# RelayBoard.net
KiCad netlist of a schematic drawn in Altium Designer
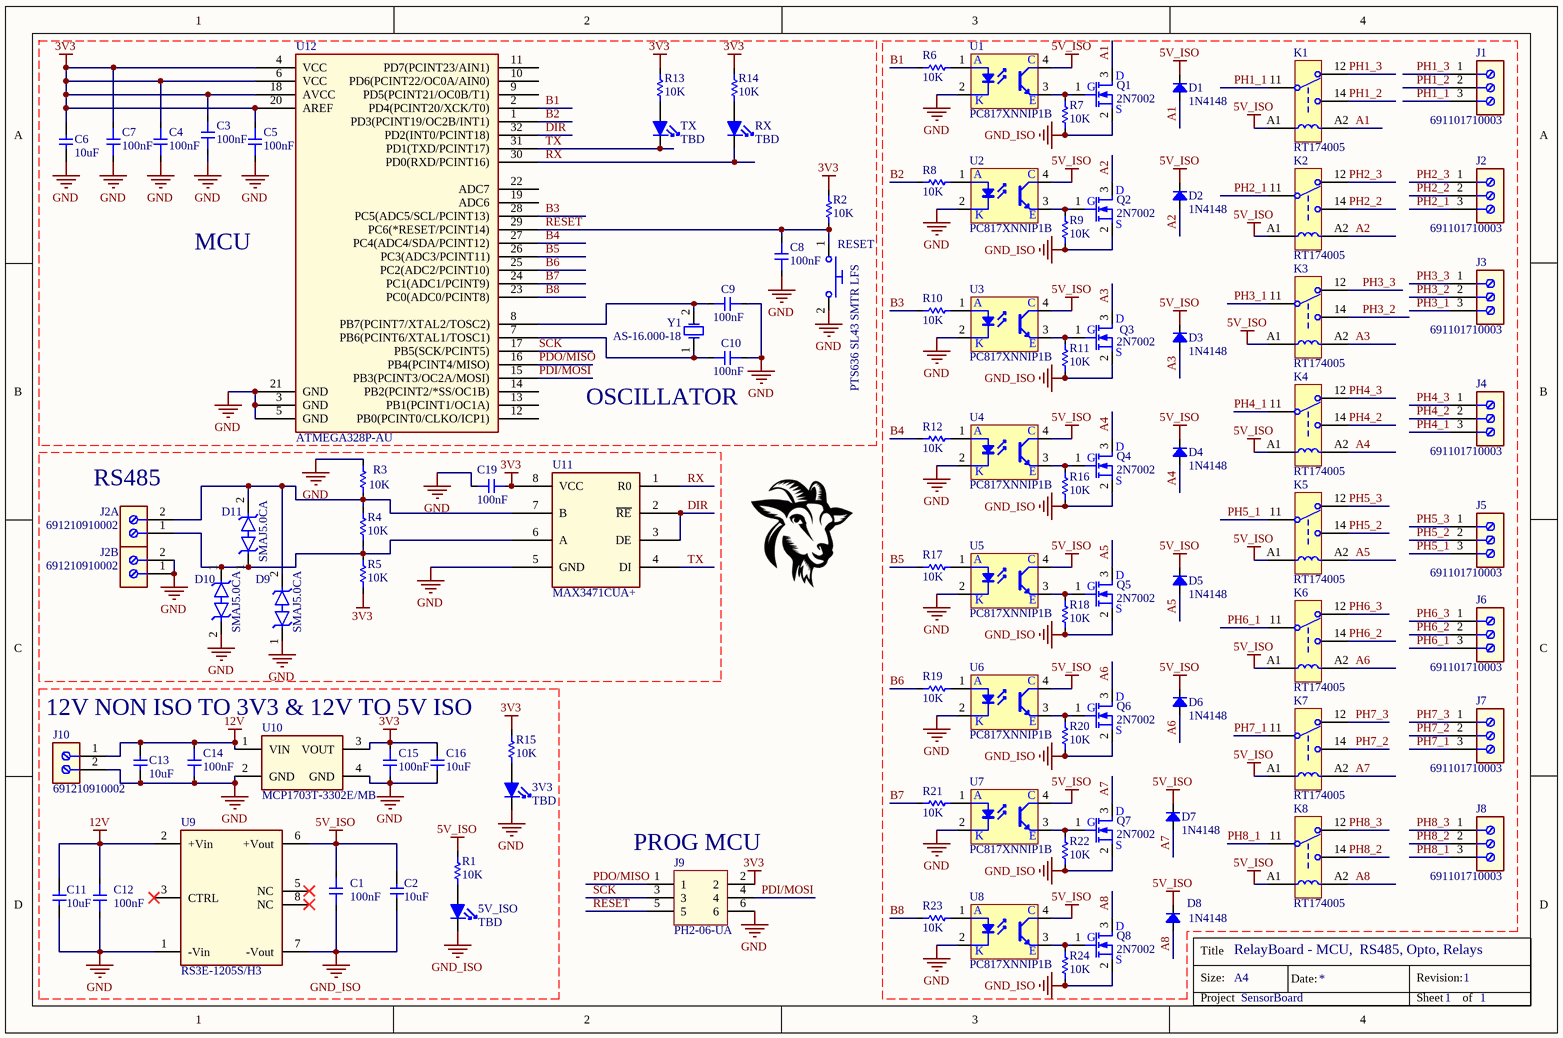
[diagram p0: RelayBoard.SchDoc]

(export (version "E")
  (design (tool "Eeschema 10.0.6"))
  (components
    (comp (ref "3V3")
      (value "TBD")
      (footprint "CASE0603")
      (description "Typical INFRARED GaAs LED")
      (libsource (lib "RelayBoard") (part "LED"))
    )
    (comp (ref "5V_ISO")
      (value "TBD")
      (footprint "CASE0603")
      (description "Typical INFRARED GaAs LED")
      (libsource (lib "RelayBoard") (part "LED"))
    )
    (comp (ref "C1")
      (value "100nF")
      (footprint "CASE0603")
      (description "CAP CER 100nF 5% 25V X7R 0603")
      (fields (field (name "MFR") "KEMET"))
      (libsource (lib "RelayBoard") (part "Capacitor_100nF"))
    )
    (comp (ref "C2")
      (value "10uF")
      (footprint "CASE0603")
      (description "CAP CER 10uF 20% 25V X5R 0603")
      (fields (field (name "MFR") "TDK"))
      (libsource (lib "RelayBoard") (part "Capacitor_10uF"))
    )
    (comp (ref "C3")
      (value "100nF")
      (footprint "CASE0603")
      (description "CAP CER 100nF 5% 25V X7R 0603")
      (fields (field (name "MFR") "KEMET"))
      (libsource (lib "RelayBoard") (part "Capacitor_100nF"))
    )
    (comp (ref "C4")
      (value "100nF")
      (footprint "CASE0603")
      (description "CAP CER 100nF 5% 25V X7R 0603")
      (fields (field (name "MFR") "KEMET"))
      (libsource (lib "RelayBoard") (part "Capacitor_100nF"))
    )
    (comp (ref "C5")
      (value "100nF")
      (footprint "CASE0603")
      (description "CAP CER 100nF 5% 25V X7R 0603")
      (fields (field (name "MFR") "KEMET"))
      (libsource (lib "RelayBoard") (part "Capacitor_100nF"))
    )
    (comp (ref "C6")
      (value "10uF")
      (footprint "CASE0603")
      (description "CAP CER 10uF 20% 25V X5R 0603")
      (fields (field (name "MFR") "TDK"))
      (libsource (lib "RelayBoard") (part "Capacitor_10uF"))
    )
    (comp (ref "C7")
      (value "100nF")
      (footprint "CASE0603")
      (description "CAP CER 100nF 5% 25V X7R 0603")
      (fields (field (name "MFR") "KEMET"))
      (libsource (lib "RelayBoard") (part "Capacitor_100nF"))
    )
    (comp (ref "C8")
      (value "100nF")
      (footprint "CASE0603")
      (description "CAP CER 100nF 5% 25V X7R 0603")
      (fields (field (name "MFR") "KEMET"))
      (libsource (lib "RelayBoard") (part "Capacitor_100nF"))
    )
    (comp (ref "C9")
      (value "100nF")
      (footprint "CASE0603")
      (description "CAP CER 100nF 5% 25V X7R 0603")
      (fields (field (name "MFR") "KEMET"))
      (libsource (lib "RelayBoard") (part "Capacitor_100nF"))
    )
    (comp (ref "C10")
      (value "100nF")
      (footprint "CASE0603")
      (description "CAP CER 100nF 5% 25V X7R 0603")
      (fields (field (name "MFR") "KEMET"))
      (libsource (lib "RelayBoard") (part "Capacitor_100nF"))
    )
    (comp (ref "C11")
      (value "10uF")
      (footprint "CASE0603")
      (description "CAP CER 10uF 20% 25V X5R 0603")
      (fields (field (name "MFR") "TDK"))
      (libsource (lib "RelayBoard") (part "Capacitor_10uF"))
    )
    (comp (ref "C12")
      (value "100nF")
      (footprint "CASE0603")
      (description "CAP CER 100nF 5% 25V X7R 0603")
      (fields (field (name "MFR") "KEMET"))
      (libsource (lib "RelayBoard") (part "Capacitor_100nF"))
    )
    (comp (ref "C13")
      (value "10uF")
      (footprint "CASE0603")
      (description "CAP CER 10uF 20% 25V X5R 0603")
      (fields (field (name "MFR") "TDK"))
      (libsource (lib "RelayBoard") (part "Capacitor_10uF"))
    )
    (comp (ref "C14")
      (value "100nF")
      (footprint "CASE0603")
      (description "CAP CER 100nF 5% 25V X7R 0603")
      (fields (field (name "MFR") "KEMET"))
      (libsource (lib "RelayBoard") (part "Capacitor_100nF"))
    )
    (comp (ref "C15")
      (value "100nF")
      (footprint "CASE0603")
      (description "CAP CER 100nF 5% 25V X7R 0603")
      (fields (field (name "MFR") "KEMET"))
      (libsource (lib "RelayBoard") (part "Capacitor_100nF"))
    )
    (comp (ref "C16")
      (value "10uF")
      (footprint "CASE0603")
      (description "CAP CER 10uF 20% 25V X5R 0603")
      (fields (field (name "MFR") "TDK"))
      (libsource (lib "RelayBoard") (part "Capacitor_10uF"))
    )
    (comp (ref "C19")
      (value "100nF")
      (footprint "CASE0603")
      (description "CAP CER 100nF 5% 25V X7R 0603")
      (fields (field (name "MFR") "KEMET"))
      (libsource (lib "RelayBoard") (part "Capacitor_100nF"))
    )
    (comp (ref "D1")
      (value "1N4148")
      (footprint "SOD-323")
      (description "High Conductance Fast Diode")
      (fields (field (name "MFR") "Micro Commercial Components (MCC)"))
      (libsource (lib "RelayBoard") (part "Diode 1N4148"))
    )
    (comp (ref "D2")
      (value "1N4148")
      (footprint "SOD-323")
      (description "High Conductance Fast Diode")
      (fields (field (name "MFR") "Micro Commercial Components (MCC)"))
      (libsource (lib "RelayBoard") (part "Diode 1N4148"))
    )
    (comp (ref "D3")
      (value "1N4148")
      (footprint "SOD-323")
      (description "High Conductance Fast Diode")
      (fields (field (name "MFR") "Micro Commercial Components (MCC)"))
      (libsource (lib "RelayBoard") (part "Diode 1N4148"))
    )
    (comp (ref "D4")
      (value "1N4148")
      (footprint "SOD-323")
      (description "High Conductance Fast Diode")
      (fields (field (name "MFR") "Micro Commercial Components (MCC)"))
      (libsource (lib "RelayBoard") (part "Diode 1N4148"))
    )
    (comp (ref "D5")
      (value "1N4148")
      (footprint "SOD-323")
      (description "High Conductance Fast Diode")
      (fields (field (name "MFR") "Micro Commercial Components (MCC)"))
      (libsource (lib "RelayBoard") (part "Diode 1N4148"))
    )
    (comp (ref "D6")
      (value "1N4148")
      (footprint "SOD-323")
      (description "High Conductance Fast Diode")
      (fields (field (name "MFR") "Micro Commercial Components (MCC)"))
      (libsource (lib "RelayBoard") (part "Diode 1N4148"))
    )
    (comp (ref "D7")
      (value "1N4148")
      (footprint "SOD-323")
      (description "High Conductance Fast Diode")
      (fields (field (name "MFR") "Micro Commercial Components (MCC)"))
      (libsource (lib "RelayBoard") (part "Diode 1N4148"))
    )
    (comp (ref "D8")
      (value "1N4148")
      (footprint "SOD-323")
      (description "High Conductance Fast Diode")
      (fields (field (name "MFR") "Micro Commercial Components (MCC)"))
      (libsource (lib "RelayBoard") (part "Diode 1N4148"))
    )
    (comp (ref "D9")
      (value "SMAJ5.0CA")
      (footprint "SMA")
      (description "9.2V Clamp 43.5A Ipp Tvs Diode Surface Mount DO-214AC (SMA)")
      (fields (field (name "MFR") "Good-Ark Semiconductor"))
      (libsource (lib "RelayBoard") (part "Diode_SMAJ5.0CA"))
    )
    (comp (ref "D10")
      (value "SMAJ5.0CA")
      (footprint "SMA")
      (description "9.2V Clamp 43.5A Ipp Tvs Diode Surface Mount DO-214AC (SMA)")
      (fields (field (name "MFR") "Good-Ark Semiconductor"))
      (libsource (lib "RelayBoard") (part "Diode_SMAJ5.0CA"))
    )
    (comp (ref "D11")
      (value "SMAJ5.0CA")
      (footprint "SMA")
      (description "9.2V Clamp 43.5A Ipp Tvs Diode Surface Mount DO-214AC (SMA)")
      (fields (field (name "MFR") "Good-Ark Semiconductor"))
      (libsource (lib "RelayBoard") (part "Diode_SMAJ5.0CA"))
    )
    (comp (ref "J1")
      (value "691101710003")
      (footprint "691101710003")
      (description "TERM BLOCK 3P HORIZON 5MM PCB")
      (fields (field (name "MFR") "Wurth"))
      (libsource (lib "RelayBoard") (part "Connector_691101710003"))
    )
    (comp (ref "J2")
      (value "691101710003")
      (footprint "691101710003")
      (description "TERM BLOCK 3P HORIZON 5MM PCB")
      (fields (field (name "MFR") "Wurth"))
      (libsource (lib "RelayBoard") (part "Connector_691101710003"))
    )
    (comp (ref "J2A")
      (value "691210910002")
      (footprint "691210910002")
      (description "TERM BLOCK 2P HORIZON 2.54MM PCB")
      (fields (field (name "MFR") "Wurth"))
      (libsource (lib "RelayBoard") (part "Connector_691210910002"))
    )
    (comp (ref "J2B")
      (value "691210910002")
      (footprint "691210910002")
      (description "TERM BLOCK 2P HORIZON 2.54MM PCB")
      (fields (field (name "MFR") "Wurth"))
      (libsource (lib "RelayBoard") (part "Connector_691210910002"))
    )
    (comp (ref "J3")
      (value "691101710003")
      (footprint "691101710003")
      (description "TERM BLOCK 3P HORIZON 5MM PCB")
      (fields (field (name "MFR") "Wurth"))
      (libsource (lib "RelayBoard") (part "Connector_691101710003"))
    )
    (comp (ref "J4")
      (value "691101710003")
      (footprint "691101710003")
      (description "TERM BLOCK 3P HORIZON 5MM PCB")
      (fields (field (name "MFR") "Wurth"))
      (libsource (lib "RelayBoard") (part "Connector_691101710003"))
    )
    (comp (ref "J5")
      (value "691101710003")
      (footprint "691101710003")
      (description "TERM BLOCK 3P HORIZON 5MM PCB")
      (fields (field (name "MFR") "Wurth"))
      (libsource (lib "RelayBoard") (part "Connector_691101710003"))
    )
    (comp (ref "J6")
      (value "691101710003")
      (footprint "691101710003")
      (description "TERM BLOCK 3P HORIZON 5MM PCB")
      (fields (field (name "MFR") "Wurth"))
      (libsource (lib "RelayBoard") (part "Connector_691101710003"))
    )
    (comp (ref "J7")
      (value "691101710003")
      (footprint "691101710003")
      (description "TERM BLOCK 3P HORIZON 5MM PCB")
      (fields (field (name "MFR") "Wurth"))
      (libsource (lib "RelayBoard") (part "Connector_691101710003"))
    )
    (comp (ref "J8")
      (value "691101710003")
      (footprint "691101710003")
      (description "TERM BLOCK 3P HORIZON 5MM PCB")
      (fields (field (name "MFR") "Wurth"))
      (libsource (lib "RelayBoard") (part "Connector_691101710003"))
    )
    (comp (ref "J9")
      (value "PH2-06-UA")
      (footprint "Header_2x3_2.54_Male")
      (description "Connector Header Through Hole 6 position 0.100\" (2.54mm)")
      (fields (field (name "MFR") "Adam Tech"))
      (libsource (lib "RelayBoard") (part "Connector_PH2-06-UA"))
    )
    (comp (ref "J10")
      (value "691210910002")
      (footprint "691210910002")
      (description "TERM BLOCK 2P HORIZON 2.54MM PCB")
      (fields (field (name "MFR") "Wurth"))
      (libsource (lib "") (part "Connector_691210910002_1"))
    )
    (comp (ref "K1")
      (value "RT174005")
      (footprint "RELAY-SPDT_3.5mm")
      (description "RELAY GEN PURPOSE SPDT 10A 5V")
      (fields (field (name "MFR") "TE"))
      (libsource (lib "RelayBoard") (part "Relay_RT174005"))
    )
    (comp (ref "K2")
      (value "RT174005")
      (footprint "RELAY-SPDT_3.5mm")
      (description "RELAY GEN PURPOSE SPDT 10A 5V")
      (fields (field (name "MFR") "TE"))
      (libsource (lib "RelayBoard") (part "Relay_RT174005"))
    )
    (comp (ref "K3")
      (value "RT174005")
      (footprint "RELAY-SPDT_3.5mm")
      (description "RELAY GEN PURPOSE SPDT 10A 5V")
      (fields (field (name "MFR") "TE"))
      (libsource (lib "RelayBoard") (part "Relay_RT174005"))
    )
    (comp (ref "K4")
      (value "RT174005")
      (footprint "RELAY-SPDT_3.5mm")
      (description "RELAY GEN PURPOSE SPDT 10A 5V")
      (fields (field (name "MFR") "TE"))
      (libsource (lib "RelayBoard") (part "Relay_RT174005"))
    )
    (comp (ref "K5")
      (value "RT174005")
      (footprint "RELAY-SPDT_3.5mm")
      (description "RELAY GEN PURPOSE SPDT 10A 5V")
      (fields (field (name "MFR") "TE"))
      (libsource (lib "RelayBoard") (part "Relay_RT174005"))
    )
    (comp (ref "K6")
      (value "RT174005")
      (footprint "RELAY-SPDT_3.5mm")
      (description "RELAY GEN PURPOSE SPDT 10A 5V")
      (fields (field (name "MFR") "TE"))
      (libsource (lib "RelayBoard") (part "Relay_RT174005"))
    )
    (comp (ref "K7")
      (value "RT174005")
      (footprint "RELAY-SPDT_3.5mm")
      (description "RELAY GEN PURPOSE SPDT 10A 5V")
      (fields (field (name "MFR") "TE"))
      (libsource (lib "RelayBoard") (part "Relay_RT174005"))
    )
    (comp (ref "K8")
      (value "RT174005")
      (footprint "RELAY-SPDT_3.5mm")
      (description "RELAY GEN PURPOSE SPDT 10A 5V")
      (fields (field (name "MFR") "TE"))
      (libsource (lib "RelayBoard") (part "Relay_RT174005"))
    )
    (comp (ref "Q1")
      (value "2N7002")
      (footprint "SOT23-3")
      (description "MOSFET N-CH 60V 280MA SOT23-3")
      (fields (field (name "MFR") "Microchip"))
      (libsource (lib "RelayBoard") (part "Transistor_NMOS"))
    )
    (comp (ref "Q2")
      (value "2N7002")
      (footprint "SOT23-3")
      (description "MOSFET N-CH 60V 280MA SOT23-3")
      (fields (field (name "MFR") "Microchip"))
      (libsource (lib "RelayBoard") (part "Transistor_NMOS"))
    )
    (comp (ref "Q3")
      (value "2N7002")
      (footprint "SOT23-3")
      (description "MOSFET N-CH 60V 280MA SOT23-3")
      (fields (field (name "MFR") "Microchip"))
      (libsource (lib "RelayBoard") (part "Transistor_NMOS"))
    )
    (comp (ref "Q4")
      (value "2N7002")
      (footprint "SOT23-3")
      (description "MOSFET N-CH 60V 280MA SOT23-3")
      (fields (field (name "MFR") "Microchip"))
      (libsource (lib "RelayBoard") (part "Transistor_NMOS"))
    )
    (comp (ref "Q5")
      (value "2N7002")
      (footprint "SOT23-3")
      (description "MOSFET N-CH 60V 280MA SOT23-3")
      (fields (field (name "MFR") "Microchip"))
      (libsource (lib "RelayBoard") (part "Transistor_NMOS"))
    )
    (comp (ref "Q6")
      (value "2N7002")
      (footprint "SOT23-3")
      (description "MOSFET N-CH 60V 280MA SOT23-3")
      (fields (field (name "MFR") "Microchip"))
      (libsource (lib "RelayBoard") (part "Transistor_NMOS"))
    )
    (comp (ref "Q7")
      (value "2N7002")
      (footprint "SOT23-3")
      (description "MOSFET N-CH 60V 280MA SOT23-3")
      (fields (field (name "MFR") "Microchip"))
      (libsource (lib "RelayBoard") (part "Transistor_NMOS"))
    )
    (comp (ref "Q8")
      (value "2N7002")
      (footprint "SOT23-3")
      (description "MOSFET N-CH 60V 280MA SOT23-3")
      (fields (field (name "MFR") "Microchip"))
      (libsource (lib "RelayBoard") (part "Transistor_NMOS"))
    )
    (comp (ref "R1")
      (value "10K")
      (footprint "CASE0603")
      (description "RES 10K 1% 1/10W 0603")
      (fields (field (name "MFR") "YAGEO"))
      (libsource (lib "RelayBoard") (part "Resistor_10K_0603"))
    )
    (comp (ref "R2")
      (value "10K")
      (footprint "CASE0603")
      (description "RES 10K 1% 1/10W 0603")
      (fields (field (name "MFR") "YAGEO"))
      (libsource (lib "RelayBoard") (part "Resistor_10K_0603"))
    )
    (comp (ref "R3")
      (value "10K")
      (footprint "CASE0603")
      (description "RES 10K 1% 1/10W 0603")
      (fields (field (name "MFR") "YAGEO"))
      (libsource (lib "RelayBoard") (part "Resistor_10K_0603"))
    )
    (comp (ref "R4")
      (value "10K")
      (footprint "CASE0603")
      (description "RES 10K 1% 1/10W 0603")
      (fields (field (name "MFR") "YAGEO"))
      (libsource (lib "RelayBoard") (part "Resistor_10K_0603"))
    )
    (comp (ref "R5")
      (value "10K")
      (footprint "CASE0603")
      (description "RES 10K 1% 1/10W 0603")
      (fields (field (name "MFR") "YAGEO"))
      (libsource (lib "RelayBoard") (part "Resistor_10K_0603"))
    )
    (comp (ref "R6")
      (value "10K")
      (footprint "CASE0603")
      (description "RES 10K 1% 1/10W 0603")
      (fields (field (name "MFR") "YAGEO"))
      (libsource (lib "RelayBoard") (part "Resistor_10K_0603"))
    )
    (comp (ref "R7")
      (value "10K")
      (footprint "CASE0603")
      (description "RES 10K 1% 1/10W 0603")
      (fields (field (name "MFR") "YAGEO"))
      (libsource (lib "RelayBoard") (part "Resistor_10K_0603"))
    )
    (comp (ref "R8")
      (value "10K")
      (footprint "CASE0603")
      (description "RES 10K 1% 1/10W 0603")
      (fields (field (name "MFR") "YAGEO"))
      (libsource (lib "RelayBoard") (part "Resistor_10K_0603"))
    )
    (comp (ref "R9")
      (value "10K")
      (footprint "CASE0603")
      (description "RES 10K 1% 1/10W 0603")
      (fields (field (name "MFR") "YAGEO"))
      (libsource (lib "RelayBoard") (part "Resistor_10K_0603"))
    )
    (comp (ref "R10")
      (value "10K")
      (footprint "CASE0603")
      (description "RES 10K 1% 1/10W 0603")
      (fields (field (name "MFR") "YAGEO"))
      (libsource (lib "RelayBoard") (part "Resistor_10K_0603"))
    )
    (comp (ref "R11")
      (value "10K")
      (footprint "CASE0603")
      (description "RES 10K 1% 1/10W 0603")
      (fields (field (name "MFR") "YAGEO"))
      (libsource (lib "RelayBoard") (part "Resistor_10K_0603"))
    )
    (comp (ref "R12")
      (value "10K")
      (footprint "CASE0603")
      (description "RES 10K 1% 1/10W 0603")
      (fields (field (name "MFR") "YAGEO"))
      (libsource (lib "RelayBoard") (part "Resistor_10K_0603"))
    )
    (comp (ref "R13")
      (value "10K")
      (footprint "CASE0603")
      (description "RES 10K 1% 1/10W 0603")
      (fields (field (name "MFR") "YAGEO"))
      (libsource (lib "RelayBoard") (part "Resistor_10K_0603"))
    )
    (comp (ref "R14")
      (value "10K")
      (footprint "CASE0603")
      (description "RES 10K 1% 1/10W 0603")
      (fields (field (name "MFR") "YAGEO"))
      (libsource (lib "RelayBoard") (part "Resistor_10K_0603"))
    )
    (comp (ref "R15")
      (value "10K")
      (footprint "CASE0603")
      (description "RES 10K 1% 1/10W 0603")
      (fields (field (name "MFR") "YAGEO"))
      (libsource (lib "RelayBoard") (part "Resistor_10K_0603"))
    )
    (comp (ref "R16")
      (value "10K")
      (footprint "CASE0603")
      (description "RES 10K 1% 1/10W 0603")
      (fields (field (name "MFR") "YAGEO"))
      (libsource (lib "RelayBoard") (part "Resistor_10K_0603"))
    )
    (comp (ref "R17")
      (value "10K")
      (footprint "CASE0603")
      (description "RES 10K 1% 1/10W 0603")
      (fields (field (name "MFR") "YAGEO"))
      (libsource (lib "RelayBoard") (part "Resistor_10K_0603"))
    )
    (comp (ref "R18")
      (value "10K")
      (footprint "CASE0603")
      (description "RES 10K 1% 1/10W 0603")
      (fields (field (name "MFR") "YAGEO"))
      (libsource (lib "RelayBoard") (part "Resistor_10K_0603"))
    )
    (comp (ref "R19")
      (value "10K")
      (footprint "CASE0603")
      (description "RES 10K 1% 1/10W 0603")
      (fields (field (name "MFR") "YAGEO"))
      (libsource (lib "RelayBoard") (part "Resistor_10K_0603"))
    )
    (comp (ref "R20")
      (value "10K")
      (footprint "CASE0603")
      (description "RES 10K 1% 1/10W 0603")
      (fields (field (name "MFR") "YAGEO"))
      (libsource (lib "RelayBoard") (part "Resistor_10K_0603"))
    )
    (comp (ref "R21")
      (value "10K")
      (footprint "CASE0603")
      (description "RES 10K 1% 1/10W 0603")
      (fields (field (name "MFR") "YAGEO"))
      (libsource (lib "RelayBoard") (part "Resistor_10K_0603"))
    )
    (comp (ref "R22")
      (value "10K")
      (footprint "CASE0603")
      (description "RES 10K 1% 1/10W 0603")
      (fields (field (name "MFR") "YAGEO"))
      (libsource (lib "RelayBoard") (part "Resistor_10K_0603"))
    )
    (comp (ref "R23")
      (value "10K")
      (footprint "CASE0603")
      (description "RES 10K 1% 1/10W 0603")
      (fields (field (name "MFR") "YAGEO"))
      (libsource (lib "RelayBoard") (part "Resistor_10K_0603"))
    )
    (comp (ref "R24")
      (value "10K")
      (footprint "CASE0603")
      (description "RES 10K 1% 1/10W 0603")
      (fields (field (name "MFR") "YAGEO"))
      (libsource (lib "RelayBoard") (part "Resistor_10K_0603"))
    )
    (comp (ref "RESET")
      (value "PTS636 SL43 SMTR LFS")
      (footprint "SMT Button")
      (description "9.2V Clamp 43.5A Ipp Tvs Diode Surface Mount DO-214AC (SMA)")
      (fields (field (name "MFR") "C&K"))
      (libsource (lib "RelayBoard") (part "Button_PTS636 SL43 SMTR LFS"))
    )
    (comp (ref "RX")
      (value "TBD")
      (footprint "CASE0603")
      (description "Typical INFRARED GaAs LED")
      (libsource (lib "RelayBoard") (part "LED"))
    )
    (comp (ref "TX")
      (value "TBD")
      (footprint "CASE0603")
      (description "Typical INFRARED GaAs LED")
      (libsource (lib "RelayBoard") (part "LED"))
    )
    (comp (ref "U1")
      (value "PC817XNNIP1B")
      (footprint "SMD-4")
      (description "4-Pin Phototransistor Optocoupler")
      (fields (field (name "MFR") "Sharp Microelectronics"))
      (libsource (lib "RelayBoard") (part "Optocoupler_PC817"))
    )
    (comp (ref "U2")
      (value "PC817XNNIP1B")
      (footprint "SMD-4")
      (description "4-Pin Phototransistor Optocoupler")
      (fields (field (name "MFR") "Sharp Microelectronics"))
      (libsource (lib "RelayBoard") (part "Optocoupler_PC817"))
    )
    (comp (ref "U3")
      (value "PC817XNNIP1B")
      (footprint "SMD-4")
      (description "4-Pin Phototransistor Optocoupler")
      (fields (field (name "MFR") "Sharp Microelectronics"))
      (libsource (lib "RelayBoard") (part "Optocoupler_PC817"))
    )
    (comp (ref "U4")
      (value "PC817XNNIP1B")
      (footprint "SMD-4")
      (description "4-Pin Phototransistor Optocoupler")
      (fields (field (name "MFR") "Sharp Microelectronics"))
      (libsource (lib "RelayBoard") (part "Optocoupler_PC817"))
    )
    (comp (ref "U5")
      (value "PC817XNNIP1B")
      (footprint "SMD-4")
      (description "4-Pin Phototransistor Optocoupler")
      (fields (field (name "MFR") "Sharp Microelectronics"))
      (libsource (lib "RelayBoard") (part "Optocoupler_PC817"))
    )
    (comp (ref "U6")
      (value "PC817XNNIP1B")
      (footprint "SMD-4")
      (description "4-Pin Phototransistor Optocoupler")
      (fields (field (name "MFR") "Sharp Microelectronics"))
      (libsource (lib "RelayBoard") (part "Optocoupler_PC817"))
    )
    (comp (ref "U7")
      (value "PC817XNNIP1B")
      (footprint "SMD-4")
      (description "4-Pin Phototransistor Optocoupler")
      (fields (field (name "MFR") "Sharp Microelectronics"))
      (libsource (lib "RelayBoard") (part "Optocoupler_PC817"))
    )
    (comp (ref "U8")
      (value "PC817XNNIP1B")
      (footprint "SMD-4")
      (description "4-Pin Phototransistor Optocoupler")
      (fields (field (name "MFR") "Sharp Microelectronics"))
      (libsource (lib "RelayBoard") (part "Optocoupler_PC817"))
    )
    (comp (ref "U9")
      (value "RS3E-1205S/H3")
      (footprint "SIP-8")
      (description "DC DC CONVERTER 9-18V IN 5V OUT 600mA 3W")
      (fields (field (name "MFR") "Recom Power"))
      (libsource (lib "RelayBoard") (part "Module_RS3E-1205S/H3"))
    )
    (comp (ref "U10")
      (value "MCP1703T-3302E/MB")
      (footprint "SOT-223-3")
      (description "IC REG LINEAR 3.3V 250MA SOT89-3")
      (fields (field (name "MFR") "Microchip"))
      (libsource (lib "RelayBoard") (part "MCP1703T-3302E/MB"))
    )
    (comp (ref "U11")
      (value "MAX3471CUA+")
      (footprint "TSSOP-8")
      (description "IC TRANSCEIVER HALF 1/1 8UMAX")
      (fields (field (name "MFR") "Analog Devices"))
      (libsource (lib "RelayBoard") (part "IC_MAX3471"))
    )
    (comp (ref "U12")
      (value "ATMEGA328P-AU")
      (footprint "TQFP-32")
      (description "AVR AVR® ATmega Microcontroller IC 8-Bit 20MHz 32KB (16K x 16) FLASH 32-TQFP (7x7)")
      (libsource (lib "RelayBoard") (part "IC_ATMEGA328"))
    )
    (comp (ref "Y1")
      (value "AS-16.000-18")
      (footprint "HC-49/US")
      (description "16 MHz ±30ppm Crystal 18pF 40 Ohms HC-49/US")
      (fields (field (name "MFR") "Raltron Electronics"))
      (libsource (lib "RelayBoard") (part "Crystal_AS-16.000-18"))
    )
  )
  (nets
    (net (code "1") (name "/A1") (class "Default")
      (node (ref "D1") (pin "A") (pinfunction "A_A") (pintype "passive"))
      (node (ref "K1") (pin "A2") (pinfunction "5_A2") (pintype "passive"))
      (node (ref "Q1") (pin "3") (pinfunction "D_3") (pintype "passive"))
    )
    (net (code "2") (name "/A2") (class "Default")
      (node (ref "D2") (pin "A") (pinfunction "A_A") (pintype "passive"))
      (node (ref "K2") (pin "A2") (pinfunction "5_A2") (pintype "passive"))
      (node (ref "Q2") (pin "3") (pinfunction "D_3") (pintype "passive"))
    )
    (net (code "3") (name "/A3") (class "Default")
      (node (ref "D3") (pin "A") (pinfunction "A_A") (pintype "passive"))
      (node (ref "K3") (pin "A2") (pinfunction "5_A2") (pintype "passive"))
      (node (ref "Q3") (pin "3") (pinfunction "D_3") (pintype "passive"))
    )
    (net (code "4") (name "/A4") (class "Default")
      (node (ref "D4") (pin "A") (pinfunction "A_A") (pintype "passive"))
      (node (ref "K4") (pin "A2") (pinfunction "5_A2") (pintype "passive"))
      (node (ref "Q4") (pin "3") (pinfunction "D_3") (pintype "passive"))
    )
    (net (code "5") (name "/A5") (class "Default")
      (node (ref "D5") (pin "A") (pinfunction "A_A") (pintype "passive"))
      (node (ref "K5") (pin "A2") (pinfunction "5_A2") (pintype "passive"))
      (node (ref "Q5") (pin "3") (pinfunction "D_3") (pintype "passive"))
    )
    (net (code "6") (name "/A6") (class "Default")
      (node (ref "D6") (pin "A") (pinfunction "A_A") (pintype "passive"))
      (node (ref "K6") (pin "A2") (pinfunction "5_A2") (pintype "passive"))
      (node (ref "Q6") (pin "3") (pinfunction "D_3") (pintype "passive"))
    )
    (net (code "7") (name "/A7") (class "Default")
      (node (ref "D7") (pin "A") (pinfunction "A_A") (pintype "passive"))
      (node (ref "K7") (pin "A2") (pinfunction "5_A2") (pintype "passive"))
      (node (ref "Q7") (pin "3") (pinfunction "D_3") (pintype "passive"))
    )
    (net (code "8") (name "/A8") (class "Default")
      (node (ref "D8") (pin "A") (pinfunction "A_A") (pintype "passive"))
      (node (ref "K8") (pin "A2") (pinfunction "5_A2") (pintype "passive"))
      (node (ref "Q8") (pin "3") (pinfunction "D_3") (pintype "passive"))
    )
    (net (code "9") (name "/B1") (class "Default")
      (node (ref "R6") (pin "1") (pinfunction "1_1") (pintype "passive"))
      (node (ref "U12") (pin "2") (pinfunction "PD4(PCINT20/XCK/T0)_2") (pintype "passive"))
    )
    (net (code "10") (name "/B2") (class "Default")
      (node (ref "R8") (pin "1") (pinfunction "1_1") (pintype "passive"))
      (node (ref "U12") (pin "1") (pinfunction "PD3(PCINT19/OC2B/INT1)_1") (pintype "passive"))
    )
    (net (code "11") (name "/B3") (class "Default")
      (node (ref "R10") (pin "1") (pinfunction "1_1") (pintype "passive"))
      (node (ref "U12") (pin "28") (pinfunction "PC5(ADC5/SCL/PCINT13)_28") (pintype "passive"))
    )
    (net (code "12") (name "/B4") (class "Default")
      (node (ref "R12") (pin "1") (pinfunction "1_1") (pintype "passive"))
      (node (ref "U12") (pin "27") (pinfunction "PC4(ADC4/SDA/PCINT12)_27") (pintype "passive"))
    )
    (net (code "13") (name "/B5") (class "Default")
      (node (ref "R17") (pin "1") (pinfunction "1_1") (pintype "passive"))
      (node (ref "U12") (pin "26") (pinfunction "PC3(ADC3/PCINT11)_26") (pintype "passive"))
    )
    (net (code "14") (name "/B6") (class "Default")
      (node (ref "R19") (pin "1") (pinfunction "1_1") (pintype "passive"))
      (node (ref "U12") (pin "25") (pinfunction "PC2(ADC2/PCINT10)_25") (pintype "passive"))
    )
    (net (code "15") (name "/B7") (class "Default")
      (node (ref "R21") (pin "1") (pinfunction "1_1") (pintype "passive"))
      (node (ref "U12") (pin "24") (pinfunction "PC1(ADC1/PCINT9)_24") (pintype "passive"))
    )
    (net (code "16") (name "/B8") (class "Default")
      (node (ref "R23") (pin "1") (pinfunction "1_1") (pintype "passive"))
      (node (ref "U12") (pin "23") (pinfunction "PC0(ADC0/PCINT8)_23") (pintype "passive"))
    )
    (net (code "17") (name "/DIR") (class "Default")
      (node (ref "U11") (pin "2") (pinfunction "~{RE}_2") (pintype "passive"))
      (node (ref "U11") (pin "3") (pinfunction "DE_3") (pintype "passive"))
      (node (ref "U12") (pin "32") (pinfunction "PD2(INT0/PCINT18)_32") (pintype "passive"))
    )
    (net (code "18") (name "/PDI{slash}MOSI") (class "Default")
      (node (ref "J9") (pin "4") (pinfunction "4_4") (pintype "passive"))
      (node (ref "U12") (pin "15") (pinfunction "PB3(PCINT3/OC2A/MOSI)_15") (pintype "passive"))
    )
    (net (code "19") (name "/PDO{slash}MISO") (class "Default")
      (node (ref "J9") (pin "1") (pinfunction "1_1") (pintype "passive"))
      (node (ref "U12") (pin "16") (pinfunction "PB4(PCINT4/MISO)_16") (pintype "passive"))
    )
    (net (code "20") (name "/PH1_1") (class "Default")
      (node (ref "J1") (pin "3") (pinfunction "3_3") (pintype "passive"))
      (node (ref "K1") (pin "11") (pinfunction "1_11") (pintype "passive"))
    )
    (net (code "21") (name "/PH1_2") (class "Default")
      (node (ref "J1") (pin "2") (pinfunction "2_2") (pintype "passive"))
      (node (ref "K1") (pin "14") (pinfunction "14_14") (pintype "passive"))
    )
    (net (code "22") (name "/PH1_3") (class "Default")
      (node (ref "J1") (pin "1") (pinfunction "1_1") (pintype "passive"))
      (node (ref "K1") (pin "12") (pinfunction "12_12") (pintype "passive"))
    )
    (net (code "23") (name "/PH2_1") (class "Default")
      (node (ref "J2") (pin "3") (pinfunction "3_3") (pintype "passive"))
      (node (ref "K2") (pin "11") (pinfunction "1_11") (pintype "passive"))
    )
    (net (code "24") (name "/PH2_2") (class "Default")
      (node (ref "J2") (pin "2") (pinfunction "2_2") (pintype "passive"))
      (node (ref "K2") (pin "14") (pinfunction "14_14") (pintype "passive"))
    )
    (net (code "25") (name "/PH2_3") (class "Default")
      (node (ref "J2") (pin "1") (pinfunction "1_1") (pintype "passive"))
      (node (ref "K2") (pin "12") (pinfunction "12_12") (pintype "passive"))
    )
    (net (code "26") (name "/PH3_1") (class "Default")
      (node (ref "J3") (pin "3") (pinfunction "3_3") (pintype "passive"))
      (node (ref "K3") (pin "11") (pinfunction "1_11") (pintype "passive"))
    )
    (net (code "27") (name "/PH3_2") (class "Default")
      (node (ref "J3") (pin "2") (pinfunction "2_2") (pintype "passive"))
      (node (ref "K3") (pin "14") (pinfunction "14_14") (pintype "passive"))
    )
    (net (code "28") (name "/PH3_3") (class "Default")
      (node (ref "J3") (pin "1") (pinfunction "1_1") (pintype "passive"))
      (node (ref "K3") (pin "12") (pinfunction "12_12") (pintype "passive"))
    )
    (net (code "29") (name "/PH4_1") (class "Default")
      (node (ref "J4") (pin "3") (pinfunction "3_3") (pintype "passive"))
      (node (ref "K4") (pin "11") (pinfunction "1_11") (pintype "passive"))
    )
    (net (code "30") (name "/PH4_2") (class "Default")
      (node (ref "J4") (pin "2") (pinfunction "2_2") (pintype "passive"))
      (node (ref "K4") (pin "14") (pinfunction "14_14") (pintype "passive"))
    )
    (net (code "31") (name "/PH4_3") (class "Default")
      (node (ref "J4") (pin "1") (pinfunction "1_1") (pintype "passive"))
      (node (ref "K4") (pin "12") (pinfunction "12_12") (pintype "passive"))
    )
    (net (code "32") (name "/PH5_1") (class "Default")
      (node (ref "J5") (pin "3") (pinfunction "3_3") (pintype "passive"))
      (node (ref "K5") (pin "11") (pinfunction "1_11") (pintype "passive"))
    )
    (net (code "33") (name "/PH5_2") (class "Default")
      (node (ref "J5") (pin "2") (pinfunction "2_2") (pintype "passive"))
      (node (ref "K5") (pin "14") (pinfunction "14_14") (pintype "passive"))
    )
    (net (code "34") (name "/PH5_3") (class "Default")
      (node (ref "J5") (pin "1") (pinfunction "1_1") (pintype "passive"))
      (node (ref "K5") (pin "12") (pinfunction "12_12") (pintype "passive"))
    )
    (net (code "35") (name "/PH6_1") (class "Default")
      (node (ref "J6") (pin "3") (pinfunction "3_3") (pintype "passive"))
      (node (ref "K6") (pin "11") (pinfunction "1_11") (pintype "passive"))
    )
    (net (code "36") (name "/PH6_2") (class "Default")
      (node (ref "J6") (pin "2") (pinfunction "2_2") (pintype "passive"))
      (node (ref "K6") (pin "14") (pinfunction "14_14") (pintype "passive"))
    )
    (net (code "37") (name "/PH6_3") (class "Default")
      (node (ref "J6") (pin "1") (pinfunction "1_1") (pintype "passive"))
      (node (ref "K6") (pin "12") (pinfunction "12_12") (pintype "passive"))
    )
    (net (code "38") (name "/PH7_1") (class "Default")
      (node (ref "J7") (pin "3") (pinfunction "3_3") (pintype "passive"))
      (node (ref "K7") (pin "11") (pinfunction "1_11") (pintype "passive"))
    )
    (net (code "39") (name "/PH7_2") (class "Default")
      (node (ref "J7") (pin "2") (pinfunction "2_2") (pintype "passive"))
      (node (ref "K7") (pin "14") (pinfunction "14_14") (pintype "passive"))
    )
    (net (code "40") (name "/PH7_3") (class "Default")
      (node (ref "J7") (pin "1") (pinfunction "1_1") (pintype "passive"))
      (node (ref "K7") (pin "12") (pinfunction "12_12") (pintype "passive"))
    )
    (net (code "41") (name "/PH8_1") (class "Default")
      (node (ref "J8") (pin "3") (pinfunction "3_3") (pintype "passive"))
      (node (ref "K8") (pin "11") (pinfunction "1_11") (pintype "passive"))
    )
    (net (code "42") (name "/PH8_2") (class "Default")
      (node (ref "J8") (pin "2") (pinfunction "2_2") (pintype "passive"))
      (node (ref "K8") (pin "14") (pinfunction "14_14") (pintype "passive"))
    )
    (net (code "43") (name "/PH8_3") (class "Default")
      (node (ref "J8") (pin "1") (pinfunction "1_1") (pintype "passive"))
      (node (ref "K8") (pin "12") (pinfunction "12_12") (pintype "passive"))
    )
    (net (code "44") (name "/RX") (class "Default")
      (node (ref "RX") (pin "2") (pinfunction "K_2") (pintype "passive"))
      (node (ref "U11") (pin "1") (pinfunction "R0_1") (pintype "passive"))
      (node (ref "U12") (pin "30") (pinfunction "PD0(RXD/PCINT16)_30") (pintype "passive"))
    )
    (net (code "45") (name "/SCK") (class "Default")
      (node (ref "J9") (pin "3") (pinfunction "3_3") (pintype "passive"))
      (node (ref "U12") (pin "17") (pinfunction "PB5(SCK/PCINT5)_17") (pintype "passive"))
    )
    (net (code "46") (name "/TX") (class "Default")
      (node (ref "TX") (pin "2") (pinfunction "K_2") (pintype "passive"))
      (node (ref "U11") (pin "4") (pinfunction "DI_4") (pintype "passive"))
      (node (ref "U12") (pin "31") (pinfunction "PD1(TXD/PCINT17)_31") (pintype "passive"))
    )
    (net (code "47") (name "/~{RESET}") (class "Default")
      (node (ref "C8") (pin "1") (pinfunction "1_1") (pintype "passive"))
      (node (ref "J9") (pin "5") (pinfunction "5_5") (pintype "passive"))
      (node (ref "R2") (pin "2") (pinfunction "2_2") (pintype "passive"))
      (node (ref "RESET") (pin "1") (pinfunction "1_1") (pintype "passive"))
      (node (ref "U12") (pin "29") (pinfunction "PC6(*RESET/PCINT14)_29") (pintype "passive"))
    )
    (net (code "48") (name "3V3") (class "Default")
      (node (ref "C15") (pin "2") (pinfunction "2_2") (pintype "passive"))
      (node (ref "C16") (pin "2") (pinfunction "2_2") (pintype "passive"))
      (node (ref "C19") (pin "1") (pinfunction "1_1") (pintype "passive"))
      (node (ref "C3") (pin "2") (pinfunction "2_2") (pintype "passive"))
      (node (ref "C4") (pin "2") (pinfunction "2_2") (pintype "passive"))
      (node (ref "C5") (pin "2") (pinfunction "2_2") (pintype "passive"))
      (node (ref "C6") (pin "2") (pinfunction "2_2") (pintype "passive"))
      (node (ref "C7") (pin "2") (pinfunction "2_2") (pintype "passive"))
      (node (ref "J9") (pin "2") (pinfunction "2_2") (pintype "passive"))
      (node (ref "R13") (pin "1") (pinfunction "1_1") (pintype "passive"))
      (node (ref "R14") (pin "1") (pinfunction "1_1") (pintype "passive"))
      (node (ref "R15") (pin "1") (pinfunction "1_1") (pintype "passive"))
      (node (ref "R2") (pin "1") (pinfunction "1_1") (pintype "passive"))
      (node (ref "R5") (pin "2") (pinfunction "2_2") (pintype "passive"))
      (node (ref "U10") (pin "3") (pinfunction "VOUT_3") (pintype "passive"))
      (node (ref "U11") (pin "8") (pinfunction "VCC_8") (pintype "passive"))
      (node (ref "U12") (pin "18") (pinfunction "AVCC_18") (pintype "passive"))
      (node (ref "U12") (pin "20") (pinfunction "AREF_20") (pintype "passive"))
      (node (ref "U12") (pin "4") (pinfunction "VCC_4") (pintype "passive"))
      (node (ref "U12") (pin "6") (pinfunction "VCC_6") (pintype "passive"))
    )
    (net (code "49") (name "5V_ISO") (class "Default")
      (node (ref "C1") (pin "2") (pinfunction "2_2") (pintype "passive"))
      (node (ref "C2") (pin "2") (pinfunction "2_2") (pintype "passive"))
      (node (ref "D1") (pin "K") (pinfunction "K_K") (pintype "passive"))
      (node (ref "D2") (pin "K") (pinfunction "K_K") (pintype "passive"))
      (node (ref "D3") (pin "K") (pinfunction "K_K") (pintype "passive"))
      (node (ref "D4") (pin "K") (pinfunction "K_K") (pintype "passive"))
      (node (ref "D5") (pin "K") (pinfunction "K_K") (pintype "passive"))
      (node (ref "D6") (pin "K") (pinfunction "K_K") (pintype "passive"))
      (node (ref "D7") (pin "K") (pinfunction "K_K") (pintype "passive"))
      (node (ref "D8") (pin "K") (pinfunction "K_K") (pintype "passive"))
      (node (ref "K1") (pin "A1") (pintype "passive"))
      (node (ref "K2") (pin "A1") (pintype "passive"))
      (node (ref "K3") (pin "A1") (pintype "passive"))
      (node (ref "K4") (pin "A1") (pintype "passive"))
      (node (ref "K5") (pin "A1") (pintype "passive"))
      (node (ref "K6") (pin "A1") (pintype "passive"))
      (node (ref "K7") (pin "A1") (pintype "passive"))
      (node (ref "K8") (pin "A1") (pintype "passive"))
      (node (ref "R1") (pin "1") (pinfunction "1_1") (pintype "passive"))
      (node (ref "U1") (pin "4") (pinfunction "C_4") (pintype "passive"))
      (node (ref "U2") (pin "4") (pinfunction "C_4") (pintype "passive"))
      (node (ref "U3") (pin "4") (pinfunction "C_4") (pintype "passive"))
      (node (ref "U4") (pin "4") (pinfunction "C_4") (pintype "passive"))
      (node (ref "U5") (pin "4") (pinfunction "C_4") (pintype "passive"))
      (node (ref "U6") (pin "4") (pinfunction "C_4") (pintype "passive"))
      (node (ref "U7") (pin "4") (pinfunction "C_4") (pintype "passive"))
      (node (ref "U8") (pin "4") (pinfunction "C_4") (pintype "passive"))
      (node (ref "U9") (pin "6") (pinfunction "+Vout_6") (pintype "passive"))
    )
    (net (code "50") (name "12V") (class "Default")
      (node (ref "C11") (pin "2") (pinfunction "2_2") (pintype "passive"))
      (node (ref "C12") (pin "2") (pinfunction "2_2") (pintype "passive"))
      (node (ref "C13") (pin "2") (pinfunction "2_2") (pintype "passive"))
      (node (ref "C14") (pin "2") (pinfunction "2_2") (pintype "passive"))
      (node (ref "J10") (pin "1") (pinfunction "1_1") (pintype "passive"))
      (node (ref "U10") (pin "1") (pinfunction "VIN_1") (pintype "passive"))
      (node (ref "U9") (pin "2") (pinfunction "+Vin_2") (pintype "passive"))
    )
    (net (code "51") (name "GND") (class "Default")
      (node (ref "3V3") (pin "2") (pinfunction "K_2") (pintype "passive"))
      (node (ref "C10") (pin "1") (pinfunction "1_1") (pintype "passive"))
      (node (ref "C11") (pin "1") (pinfunction "1_1") (pintype "passive"))
      (node (ref "C12") (pin "1") (pinfunction "1_1") (pintype "passive"))
      (node (ref "C13") (pin "1") (pinfunction "1_1") (pintype "passive"))
      (node (ref "C14") (pin "1") (pinfunction "1_1") (pintype "passive"))
      (node (ref "C15") (pin "1") (pinfunction "1_1") (pintype "passive"))
      (node (ref "C16") (pin "1") (pinfunction "1_1") (pintype "passive"))
      (node (ref "C19") (pin "2") (pinfunction "2_2") (pintype "passive"))
      (node (ref "C3") (pin "1") (pinfunction "1_1") (pintype "passive"))
      (node (ref "C4") (pin "1") (pinfunction "1_1") (pintype "passive"))
      (node (ref "C5") (pin "1") (pinfunction "1_1") (pintype "passive"))
      (node (ref "C6") (pin "1") (pinfunction "1_1") (pintype "passive"))
      (node (ref "C7") (pin "1") (pinfunction "1_1") (pintype "passive"))
      (node (ref "C8") (pin "2") (pinfunction "2_2") (pintype "passive"))
      (node (ref "C9") (pin "1") (pinfunction "1_1") (pintype "passive"))
      (node (ref "D10") (pin "2") (pinfunction "2_2") (pintype "passive"))
      (node (ref "D9") (pin "1") (pinfunction "1_1") (pintype "passive"))
      (node (ref "J10") (pin "2") (pinfunction "2_2") (pintype "passive"))
      (node (ref "J2B") (pin "1") (pinfunction "1_1") (pintype "passive"))
      (node (ref "J2B") (pin "2") (pinfunction "2_2") (pintype "passive"))
      (node (ref "J9") (pin "6") (pinfunction "6_6") (pintype "passive"))
      (node (ref "R3") (pin "1") (pinfunction "1_1") (pintype "passive"))
      (node (ref "RESET") (pin "2") (pinfunction "2_2") (pintype "passive"))
      (node (ref "U1") (pin "2") (pinfunction "K_2") (pintype "passive"))
      (node (ref "U10") (pin "2") (pinfunction "GND_2") (pintype "passive"))
      (node (ref "U10") (pin "4") (pinfunction "GND_4") (pintype "passive"))
      (node (ref "U11") (pin "5") (pinfunction "GND_5") (pintype "passive"))
      (node (ref "U12") (pin "21") (pinfunction "GND_21") (pintype "passive"))
      (node (ref "U12") (pin "3") (pinfunction "GND_3") (pintype "passive"))
      (node (ref "U12") (pin "5") (pinfunction "GND_5") (pintype "passive"))
      (node (ref "U2") (pin "2") (pinfunction "K_2") (pintype "passive"))
      (node (ref "U3") (pin "2") (pinfunction "K_2") (pintype "passive"))
      (node (ref "U4") (pin "2") (pinfunction "K_2") (pintype "passive"))
      (node (ref "U5") (pin "2") (pinfunction "K_2") (pintype "passive"))
      (node (ref "U6") (pin "2") (pinfunction "K_2") (pintype "passive"))
      (node (ref "U7") (pin "2") (pinfunction "K_2") (pintype "passive"))
      (node (ref "U8") (pin "2") (pinfunction "K_2") (pintype "passive"))
      (node (ref "U9") (pin "1") (pinfunction "-Vin_1") (pintype "passive"))
    )
    (net (code "52") (name "GND_ISO") (class "Default")
      (node (ref "5V_ISO") (pin "2") (pinfunction "K_2") (pintype "passive"))
      (node (ref "C1") (pin "1") (pinfunction "1_1") (pintype "passive"))
      (node (ref "C2") (pin "1") (pinfunction "1_1") (pintype "passive"))
      (node (ref "Q1") (pin "2") (pinfunction "S_2") (pintype "passive"))
      (node (ref "Q2") (pin "2") (pinfunction "S_2") (pintype "passive"))
      (node (ref "Q3") (pin "2") (pinfunction "S_2") (pintype "passive"))
      (node (ref "Q4") (pin "2") (pinfunction "S_2") (pintype "passive"))
      (node (ref "Q5") (pin "2") (pinfunction "S_2") (pintype "passive"))
      (node (ref "Q6") (pin "2") (pinfunction "S_2") (pintype "passive"))
      (node (ref "Q7") (pin "2") (pinfunction "S_2") (pintype "passive"))
      (node (ref "Q8") (pin "2") (pinfunction "S_2") (pintype "passive"))
      (node (ref "R11") (pin "1") (pinfunction "1_1") (pintype "passive"))
      (node (ref "R16") (pin "1") (pinfunction "1_1") (pintype "passive"))
      (node (ref "R18") (pin "1") (pinfunction "1_1") (pintype "passive"))
      (node (ref "R20") (pin "1") (pinfunction "1_1") (pintype "passive"))
      (node (ref "R22") (pin "1") (pinfunction "1_1") (pintype "passive"))
      (node (ref "R24") (pin "1") (pinfunction "1_1") (pintype "passive"))
      (node (ref "R7") (pin "1") (pinfunction "1_1") (pintype "passive"))
      (node (ref "R9") (pin "1") (pinfunction "1_1") (pintype "passive"))
      (node (ref "U9") (pin "7") (pinfunction "-Vout_7") (pintype "passive"))
    )
    (net (code "53") (name "Net-(3V3-A)") (class "Default")
      (node (ref "3V3") (pin "1") (pinfunction "A_1") (pintype "passive"))
      (node (ref "R15") (pin "2") (pinfunction "2_2") (pintype "passive"))
    )
    (net (code "54") (name "Net-(5V_ISO-A)") (class "Default")
      (node (ref "5V_ISO") (pin "1") (pinfunction "A_1") (pintype "passive"))
      (node (ref "R1") (pin "2") (pinfunction "2_2") (pintype "passive"))
    )
    (net (code "55") (name "Net-(Q1-G)") (class "Default")
      (node (ref "Q1") (pin "1") (pinfunction "G_1") (pintype "passive"))
      (node (ref "R7") (pin "2") (pinfunction "2_2") (pintype "passive"))
      (node (ref "U1") (pin "3") (pinfunction "E_3") (pintype "passive"))
    )
    (net (code "56") (name "Net-(Q2-G)") (class "Default")
      (node (ref "Q2") (pin "1") (pinfunction "G_1") (pintype "passive"))
      (node (ref "R9") (pin "2") (pinfunction "2_2") (pintype "passive"))
      (node (ref "U2") (pin "3") (pinfunction "E_3") (pintype "passive"))
    )
    (net (code "57") (name "Net-(Q3-G)") (class "Default")
      (node (ref "Q3") (pin "1") (pinfunction "G_1") (pintype "passive"))
      (node (ref "R11") (pin "2") (pinfunction "2_2") (pintype "passive"))
      (node (ref "U3") (pin "3") (pinfunction "E_3") (pintype "passive"))
    )
    (net (code "58") (name "Net-(Q4-G)") (class "Default")
      (node (ref "Q4") (pin "1") (pinfunction "G_1") (pintype "passive"))
      (node (ref "R16") (pin "2") (pinfunction "2_2") (pintype "passive"))
      (node (ref "U4") (pin "3") (pinfunction "E_3") (pintype "passive"))
    )
    (net (code "59") (name "Net-(Q5-G)") (class "Default")
      (node (ref "Q5") (pin "1") (pinfunction "G_1") (pintype "passive"))
      (node (ref "R18") (pin "2") (pinfunction "2_2") (pintype "passive"))
      (node (ref "U5") (pin "3") (pinfunction "E_3") (pintype "passive"))
    )
    (net (code "60") (name "Net-(Q6-G)") (class "Default")
      (node (ref "Q6") (pin "1") (pinfunction "G_1") (pintype "passive"))
      (node (ref "R20") (pin "2") (pinfunction "2_2") (pintype "passive"))
      (node (ref "U6") (pin "3") (pinfunction "E_3") (pintype "passive"))
    )
    (net (code "61") (name "Net-(Q7-G)") (class "Default")
      (node (ref "Q7") (pin "1") (pinfunction "G_1") (pintype "passive"))
      (node (ref "R22") (pin "2") (pinfunction "2_2") (pintype "passive"))
      (node (ref "U7") (pin "3") (pinfunction "E_3") (pintype "passive"))
    )
    (net (code "62") (name "Net-(Q8-G)") (class "Default")
      (node (ref "Q8") (pin "1") (pinfunction "G_1") (pintype "passive"))
      (node (ref "R24") (pin "2") (pinfunction "2_2") (pintype "passive"))
      (node (ref "U8") (pin "3") (pinfunction "E_3") (pintype "passive"))
    )
    (net (code "63") (name "Net-(RX-A)") (class "Default")
      (node (ref "R14") (pin "2") (pinfunction "2_2") (pintype "passive"))
      (node (ref "RX") (pin "1") (pinfunction "A_1") (pintype "passive"))
    )
    (net (code "64") (name "Net-(TX-A)") (class "Default")
      (node (ref "R13") (pin "2") (pinfunction "2_2") (pintype "passive"))
      (node (ref "TX") (pin "1") (pinfunction "A_1") (pintype "passive"))
    )
    (net (code "65") (name "Net-(U1-A)") (class "Default")
      (node (ref "R6") (pin "2") (pinfunction "2_2") (pintype "passive"))
      (node (ref "U1") (pin "1") (pinfunction "A_1") (pintype "passive"))
    )
    (net (code "66") (name "Net-(U2-A)") (class "Default")
      (node (ref "R8") (pin "2") (pinfunction "2_2") (pintype "passive"))
      (node (ref "U2") (pin "1") (pinfunction "A_1") (pintype "passive"))
    )
    (net (code "67") (name "Net-(U3-A)") (class "Default")
      (node (ref "R10") (pin "2") (pinfunction "2_2") (pintype "passive"))
      (node (ref "U3") (pin "1") (pinfunction "A_1") (pintype "passive"))
    )
    (net (code "68") (name "Net-(U4-A)") (class "Default")
      (node (ref "R12") (pin "2") (pinfunction "2_2") (pintype "passive"))
      (node (ref "U4") (pin "1") (pinfunction "A_1") (pintype "passive"))
    )
    (net (code "69") (name "Net-(U5-A)") (class "Default")
      (node (ref "R17") (pin "2") (pinfunction "2_2") (pintype "passive"))
      (node (ref "U5") (pin "1") (pinfunction "A_1") (pintype "passive"))
    )
    (net (code "70") (name "Net-(U6-A)") (class "Default")
      (node (ref "R19") (pin "2") (pinfunction "2_2") (pintype "passive"))
      (node (ref "U6") (pin "1") (pinfunction "A_1") (pintype "passive"))
    )
    (net (code "71") (name "Net-(U7-A)") (class "Default")
      (node (ref "R21") (pin "2") (pinfunction "2_2") (pintype "passive"))
      (node (ref "U7") (pin "1") (pinfunction "A_1") (pintype "passive"))
    )
    (net (code "72") (name "Net-(U8-A)") (class "Default")
      (node (ref "R23") (pin "2") (pinfunction "2_2") (pintype "passive"))
      (node (ref "U8") (pin "1") (pinfunction "A_1") (pintype "passive"))
    )
    (net (code "73") (name "Net-(U11-A)") (class "Default")
      (node (ref "D10") (pin "1") (pinfunction "1_1") (pintype "passive"))
      (node (ref "D11") (pin "1") (pinfunction "1_1") (pintype "passive"))
      (node (ref "J2A") (pin "1") (pinfunction "1_1") (pintype "passive"))
      (node (ref "R4") (pin "2") (pinfunction "2_2") (pintype "passive"))
      (node (ref "R5") (pin "1") (pinfunction "1_1") (pintype "passive"))
      (node (ref "U11") (pin "6") (pinfunction "A_6") (pintype "passive"))
    )
    (net (code "74") (name "Net-(U11-B)") (class "Default")
      (node (ref "D11") (pin "2") (pinfunction "2_2") (pintype "passive"))
      (node (ref "D9") (pin "2") (pinfunction "2_2") (pintype "passive"))
      (node (ref "J2A") (pin "2") (pinfunction "2_2") (pintype "passive"))
      (node (ref "R3") (pin "2") (pinfunction "2_2") (pintype "passive"))
      (node (ref "R4") (pin "1") (pinfunction "1_1") (pintype "passive"))
      (node (ref "U11") (pin "7") (pinfunction "B_7") (pintype "passive"))
    )
    (net (code "75") (name "Net-(U12-PB6(PCINT6{slash}XTAL1{slash}TOSC1))") (class "Default")
      (node (ref "C10") (pin "2") (pinfunction "2_2") (pintype "passive"))
      (node (ref "U12") (pin "7") (pinfunction "PB6(PCINT6/XTAL1/TOSC1)_7") (pintype "passive"))
      (node (ref "Y1") (pin "1") (pinfunction "OSC1_1") (pintype "passive"))
    )
    (net (code "76") (name "Net-(U12-PB7(PCINT7{slash}XTAL2{slash}TOSC2))") (class "Default")
      (node (ref "C9") (pin "2") (pinfunction "2_2") (pintype "passive"))
      (node (ref "U12") (pin "8") (pinfunction "PB7(PCINT7/XTAL2/TOSC2)_8") (pintype "passive"))
      (node (ref "Y1") (pin "2") (pinfunction "OSC2_2") (pintype "passive"))
    )
    (net (code "77") (name "unconnected-(U9-CTRL-Pad3)") (class "Default")
      (node (ref "U9") (pin "3") (pinfunction "CTRL_3") (pintype "passive+no_connect"))
    )
    (net (code "78") (name "unconnected-(U9-NC-Pad5)") (class "Default")
      (node (ref "U9") (pin "5") (pinfunction "NC_5") (pintype "passive+no_connect"))
    )
    (net (code "79") (name "unconnected-(U9-NC-Pad8)") (class "Default")
      (node (ref "U9") (pin "8") (pinfunction "NC_8") (pintype "passive+no_connect"))
    )
    (net (code "80") (name "unconnected-(U12-ADC6-Pad19)") (class "Default")
      (node (ref "U12") (pin "19") (pinfunction "ADC6_19") (pintype "passive"))
    )
    (net (code "81") (name "unconnected-(U12-ADC7-Pad22)") (class "Default")
      (node (ref "U12") (pin "22") (pinfunction "ADC7_22") (pintype "passive"))
    )
    (net (code "82") (name "unconnected-(U12-PB0(PCINT0{slash}CLKO{slash}ICP1)-Pad12)") (class "Default")
      (node (ref "U12") (pin "12") (pinfunction "PB0(PCINT0/CLKO/ICP1)_12") (pintype "passive"))
    )
    (net (code "83") (name "unconnected-(U12-PB1(PCINT1{slash}OC1A)-Pad13)") (class "Default")
      (node (ref "U12") (pin "13") (pinfunction "PB1(PCINT1/OC1A)_13") (pintype "passive"))
    )
    (net (code "84") (name "unconnected-(U12-PB2(PCINT2{slash}*SS{slash}OC1B)-Pad14)") (class "Default")
      (node (ref "U12") (pin "14") (pinfunction "PB2(PCINT2/*SS/OC1B)_14") (pintype "passive"))
    )
    (net (code "85") (name "unconnected-(U12-PD5(PCINT21{slash}OC0B{slash}T1)-Pad9)") (class "Default")
      (node (ref "U12") (pin "9") (pinfunction "PD5(PCINT21/OC0B/T1)_9") (pintype "passive"))
    )
    (net (code "86") (name "unconnected-(U12-PD6(PCINT22{slash}OC0A{slash}AIN0)-Pad10)") (class "Default")
      (node (ref "U12") (pin "10") (pinfunction "PD6(PCINT22/OC0A/AIN0)_10") (pintype "passive"))
    )
    (net (code "87") (name "unconnected-(U12-PD7(PCINT23{slash}AIN1)-Pad11)") (class "Default")
      (node (ref "U12") (pin "11") (pinfunction "PD7(PCINT23/AIN1)_11") (pintype "passive"))
    )
  )
)
